# minibat.net
KiCad netlist of a schematic drawn in EAGLE
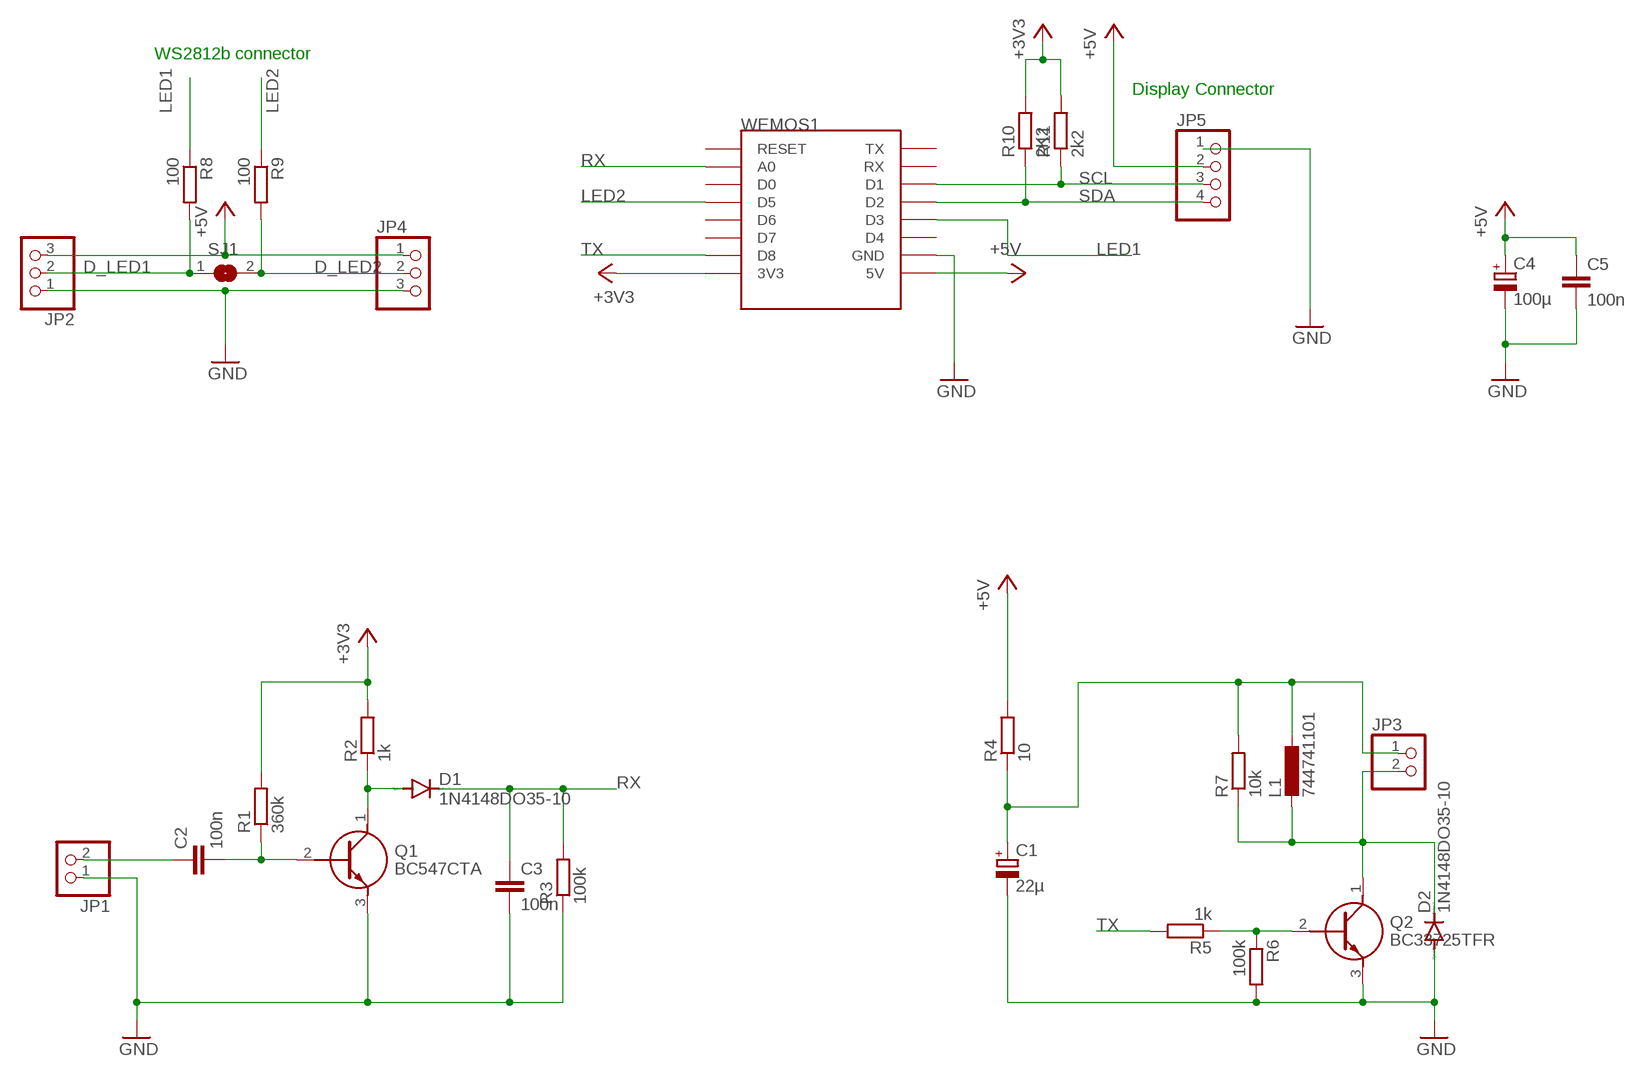
[diagram p0: schematic, sheet 1]

(export (version "E")
  (design (tool "Eeschema 10.0.6"))
  (components
    (comp (ref "C1")
      (value "22µ")
      (footprint "eagle-import:E5-8,5")
      (libsource (lib "eagle-import") (part "CPOL-EUE5-8.5"))
    )
    (comp (ref "C2")
      (value "100n")
      (footprint "eagle-import:C050-035X075")
      (libsource (lib "eagle-import") (part "C-EU050-035X075"))
    )
    (comp (ref "C3")
      (value "100n")
      (footprint "eagle-import:C050-035X075")
      (libsource (lib "eagle-import") (part "C-EU050-035X075"))
    )
    (comp (ref "C4")
      (value "100µ")
      (footprint "eagle-import:E5-8,5")
      (libsource (lib "eagle-import") (part "CPOL-EUE5-8.5"))
    )
    (comp (ref "C5")
      (value "100n")
      (footprint "eagle-import:C050-035X075")
      (libsource (lib "eagle-import") (part "C-EU050-035X075"))
    )
    (comp (ref "D1")
      (value "1N4148DO35-10")
      (footprint "eagle-import:DO35-10")
      (libsource (lib "eagle-import") (part "1N4148DO35-10"))
    )
    (comp (ref "D2")
      (value "1N4148DO35-10")
      (footprint "eagle-import:DO35-10")
      (libsource (lib "eagle-import") (part "1N4148DO35-10"))
    )
    (comp (ref "JP1")
      (value "PINHD-1X2")
      (footprint "eagle-import:1X02")
      (libsource (lib "eagle-import") (part "PINHD-1X2"))
    )
    (comp (ref "JP2")
      (value "PINHD-1X3")
      (footprint "eagle-import:1X03")
      (libsource (lib "eagle-import") (part "PINHD-1X3"))
    )
    (comp (ref "JP3")
      (value "PINHD-1X2")
      (footprint "eagle-import:1X02")
      (libsource (lib "eagle-import") (part "PINHD-1X2"))
    )
    (comp (ref "JP4")
      (value "PINHD-1X3")
      (footprint "eagle-import:1X03")
      (libsource (lib "eagle-import") (part "PINHD-1X3"))
    )
    (comp (ref "JP5")
      (value "PINHD-1X4")
      (footprint "eagle-import:1X04")
      (libsource (lib "eagle-import") (part "PINHD-1X4"))
    )
    (comp (ref "L1")
      (value "744741101")
      (footprint "eagle-import:6000-XXXX-RC")
      (libsource (lib "eagle-import") (part "L-EU6000-XXX-RC"))
    )
    (comp (ref "Q1")
      (value "BC547CTA")
      (footprint "eagle-import:MC79L15ACPG")
      (fields (field (name "MOUSER_PART_NUMBER") "512-BC547CTA"))
      (libsource (lib "eagle-import") (part "BC547CTA"))
    )
    (comp (ref "Q2")
      (value "BC33725TFR")
      (footprint "eagle-import:BC33725TFR")
      (fields (field (name "MOUSER_PART_NUMBER") "512-BC33725TFR"))
      (libsource (lib "eagle-import") (part "BC33725TFR"))
    )
    (comp (ref "R1")
      (value "360k")
      (footprint "eagle-import:0207_10")
      (libsource (lib "eagle-import") (part "R-EU_0207/10"))
    )
    (comp (ref "R2")
      (value "1k")
      (footprint "eagle-import:0207_10")
      (libsource (lib "eagle-import") (part "R-EU_0207/10"))
    )
    (comp (ref "R3")
      (value "100k")
      (footprint "eagle-import:0207_10")
      (libsource (lib "eagle-import") (part "R-EU_0207/10"))
    )
    (comp (ref "R4")
      (value "10")
      (footprint "eagle-import:0207_10")
      (libsource (lib "eagle-import") (part "R-EU_0207/10"))
    )
    (comp (ref "R5")
      (value "1k")
      (footprint "eagle-import:0207_10")
      (libsource (lib "eagle-import") (part "R-EU_0207/10"))
    )
    (comp (ref "R6")
      (value "100k")
      (footprint "eagle-import:0207_10")
      (libsource (lib "eagle-import") (part "R-EU_0207/10"))
    )
    (comp (ref "R7")
      (value "10k")
      (footprint "eagle-import:0207_10")
      (libsource (lib "eagle-import") (part "R-EU_0207/10"))
    )
    (comp (ref "R8")
      (value "100")
      (footprint "eagle-import:0207_10")
      (libsource (lib "eagle-import") (part "R-EU_0207/10"))
    )
    (comp (ref "R9")
      (value "100")
      (footprint "eagle-import:0207_10")
      (libsource (lib "eagle-import") (part "R-EU_0207/10"))
    )
    (comp (ref "R10")
      (value "2K2")
      (footprint "eagle-import:0207_10")
      (libsource (lib "eagle-import") (part "R-EU_0207/10"))
    )
    (comp (ref "R11")
      (value "2k2")
      (footprint "eagle-import:0207_10")
      (libsource (lib "eagle-import") (part "R-EU_0207/10"))
    )
    (comp (ref "SJ1") (value "SJ") (footprint "eagle-import:SJ") (libsource (lib "eagle-import") (part "SJ")))
    (comp (ref "WEMOS1")
      (value "WEMOS-D1-MINI")
      (footprint "eagle-import:WEMOS-D1-MINI")
      (libsource (lib "eagle-import") (part "WEMOS-D1-MINI"))
    )
  )
  (nets
    (net (code "1") (name "+3V3") (class "Default")
      (node (ref "R1") (pin "2") (pinfunction "2_2") (pintype "passive"))
      (node (ref "R10") (pin "2") (pinfunction "2_2") (pintype "passive"))
      (node (ref "R11") (pin "2") (pinfunction "2_2") (pintype "passive"))
      (node (ref "R2") (pin "2") (pinfunction "2_2") (pintype "passive"))
      (node (ref "WEMOS1") (pin "3V3") (pinfunction "3V3_3V3") (pintype "bidirectional"))
    )
    (net (code "2") (name "+5V") (class "Default")
      (node (ref "C4") (pin "+") (pinfunction "+_+") (pintype "passive"))
      (node (ref "C5") (pin "1") (pinfunction "1_1") (pintype "passive"))
      (node (ref "JP2") (pin "3") (pinfunction "3_3") (pintype "passive"))
      (node (ref "JP4") (pin "1") (pinfunction "1_1") (pintype "passive"))
      (node (ref "JP5") (pin "2") (pinfunction "2_2") (pintype "passive"))
      (node (ref "R4") (pin "2") (pinfunction "2_2") (pintype "passive"))
      (node (ref "WEMOS1") (pin "5V") (pinfunction "5V_5V") (pintype "bidirectional"))
    )
    (net (code "3") (name "/D_LED1") (class "Default")
      (node (ref "JP2") (pin "2") (pinfunction "2_2") (pintype "passive"))
      (node (ref "R8") (pin "2") (pinfunction "2_2") (pintype "passive"))
      (node (ref "SJ1") (pin "1") (pinfunction "1_1") (pintype "passive"))
    )
    (net (code "4") (name "/D_LED2") (class "Default")
      (node (ref "JP4") (pin "2") (pinfunction "2_2") (pintype "passive"))
      (node (ref "R9") (pin "2") (pinfunction "2_2") (pintype "passive"))
      (node (ref "SJ1") (pin "2") (pinfunction "2_2") (pintype "passive"))
    )
    (net (code "5") (name "/LED1") (class "Default")
      (node (ref "R8") (pin "1") (pinfunction "1_1") (pintype "passive"))
      (node (ref "WEMOS1") (pin "D3") (pinfunction "D3_D3") (pintype "bidirectional"))
    )
    (net (code "6") (name "/LED2") (class "Default")
      (node (ref "R9") (pin "1") (pinfunction "1_1") (pintype "passive"))
      (node (ref "WEMOS1") (pin "D5") (pinfunction "D5_D5") (pintype "bidirectional"))
    )
    (net (code "7") (name "/RX") (class "Default")
      (node (ref "C3") (pin "1") (pinfunction "1_1") (pintype "passive"))
      (node (ref "D1") (pin "C") (pinfunction "C_C") (pintype "passive"))
      (node (ref "R3") (pin "2") (pinfunction "2_2") (pintype "passive"))
      (node (ref "WEMOS1") (pin "A0") (pinfunction "A0_A0") (pintype "bidirectional"))
    )
    (net (code "8") (name "/SCL") (class "Default")
      (node (ref "JP5") (pin "3") (pinfunction "3_3") (pintype "passive"))
      (node (ref "R11") (pin "1") (pinfunction "1_1") (pintype "passive"))
      (node (ref "WEMOS1") (pin "D1") (pinfunction "D1_D1") (pintype "bidirectional"))
    )
    (net (code "9") (name "/SDA") (class "Default")
      (node (ref "JP5") (pin "4") (pinfunction "4_4") (pintype "passive"))
      (node (ref "R10") (pin "1") (pinfunction "1_1") (pintype "passive"))
      (node (ref "WEMOS1") (pin "D2") (pinfunction "D2_D2") (pintype "bidirectional"))
    )
    (net (code "10") (name "/TX") (class "Default")
      (node (ref "R5") (pin "2") (pinfunction "2_2") (pintype "passive"))
      (node (ref "WEMOS1") (pin "D8") (pinfunction "D8_D8") (pintype "bidirectional"))
    )
    (net (code "11") (name "GND") (class "Default")
      (node (ref "C1") (pin "-") (pinfunction "-_-") (pintype "passive"))
      (node (ref "C3") (pin "2") (pinfunction "2_2") (pintype "passive"))
      (node (ref "C4") (pin "-") (pinfunction "-_-") (pintype "passive"))
      (node (ref "C5") (pin "2") (pinfunction "2_2") (pintype "passive"))
      (node (ref "D2") (pin "A") (pinfunction "A_A") (pintype "passive"))
      (node (ref "JP1") (pin "1") (pinfunction "1_1") (pintype "passive"))
      (node (ref "JP2") (pin "1") (pinfunction "1_1") (pintype "passive"))
      (node (ref "JP4") (pin "3") (pinfunction "3_3") (pintype "passive"))
      (node (ref "JP5") (pin "1") (pinfunction "1_1") (pintype "passive"))
      (node (ref "Q1") (pin "3") (pinfunction "E_3") (pintype "bidirectional"))
      (node (ref "Q2") (pin "3") (pinfunction "E_3") (pintype "bidirectional"))
      (node (ref "R3") (pin "1") (pinfunction "1_1") (pintype "passive"))
      (node (ref "R6") (pin "2") (pinfunction "2_2") (pintype "passive"))
      (node (ref "WEMOS1") (pin "GND") (pinfunction "GND_GND") (pintype "bidirectional"))
    )
    (net (code "12") (name "Net-(C1-Pad+)") (class "Default")
      (node (ref "C1") (pin "+") (pinfunction "+_+") (pintype "passive"))
      (node (ref "JP3") (pin "1") (pinfunction "1_1") (pintype "passive"))
      (node (ref "L1") (pin "1") (pinfunction "1_1") (pintype "passive"))
      (node (ref "R4") (pin "1") (pinfunction "1_1") (pintype "passive"))
      (node (ref "R7") (pin "2") (pinfunction "2_2") (pintype "passive"))
    )
    (net (code "13") (name "Net-(C2-Pad1)") (class "Default")
      (node (ref "C2") (pin "1") (pinfunction "1_1") (pintype "passive"))
      (node (ref "JP1") (pin "2") (pinfunction "2_2") (pintype "passive"))
    )
    (net (code "14") (name "Net-(Q1-B)") (class "Default")
      (node (ref "C2") (pin "2") (pinfunction "2_2") (pintype "passive"))
      (node (ref "Q1") (pin "2") (pinfunction "B_2") (pintype "bidirectional"))
      (node (ref "R1") (pin "1") (pinfunction "1_1") (pintype "passive"))
    )
    (net (code "15") (name "Net-(Q1-C)") (class "Default")
      (node (ref "D1") (pin "A") (pinfunction "A_A") (pintype "passive"))
      (node (ref "Q1") (pin "1") (pinfunction "C_1") (pintype "bidirectional"))
      (node (ref "R2") (pin "1") (pinfunction "1_1") (pintype "passive"))
    )
    (net (code "16") (name "Net-(Q2-B)") (class "Default")
      (node (ref "Q2") (pin "2") (pinfunction "B_2") (pintype "bidirectional"))
      (node (ref "R5") (pin "1") (pinfunction "1_1") (pintype "passive"))
      (node (ref "R6") (pin "1") (pinfunction "1_1") (pintype "passive"))
    )
    (net (code "17") (name "Net-(Q2-C)") (class "Default")
      (node (ref "D2") (pin "C") (pinfunction "C_C") (pintype "passive"))
      (node (ref "JP3") (pin "2") (pinfunction "2_2") (pintype "passive"))
      (node (ref "L1") (pin "2") (pinfunction "2_2") (pintype "passive"))
      (node (ref "Q2") (pin "1") (pinfunction "C_1") (pintype "bidirectional"))
      (node (ref "R7") (pin "1") (pinfunction "1_1") (pintype "passive"))
    )
    (net (code "18") (name "unconnected-(WEMOS1-PadD0)") (class "Default")
      (node (ref "WEMOS1") (pin "D0") (pinfunction "D0_D0") (pintype "bidirectional"))
    )
    (net (code "19") (name "unconnected-(WEMOS1-PadD4)") (class "Default")
      (node (ref "WEMOS1") (pin "D4") (pinfunction "D4_D4") (pintype "bidirectional"))
    )
    (net (code "20") (name "unconnected-(WEMOS1-PadD6)") (class "Default")
      (node (ref "WEMOS1") (pin "D6") (pinfunction "D6_D6") (pintype "bidirectional"))
    )
    (net (code "21") (name "unconnected-(WEMOS1-PadD7)") (class "Default")
      (node (ref "WEMOS1") (pin "D7") (pinfunction "D7_D7") (pintype "bidirectional"))
    )
    (net (code "22") (name "unconnected-(WEMOS1-PadRESET)") (class "Default")
      (node (ref "WEMOS1") (pin "RESET") (pinfunction "RESET_RESET") (pintype "bidirectional"))
    )
    (net (code "23") (name "unconnected-(WEMOS1-PadRX)") (class "Default")
      (node (ref "WEMOS1") (pin "RX") (pinfunction "RX_RX") (pintype "bidirectional"))
    )
    (net (code "24") (name "unconnected-(WEMOS1-PadTX)") (class "Default")
      (node (ref "WEMOS1") (pin "TX") (pinfunction "TX_TX") (pintype "bidirectional"))
    )
  )
)
